# MikrofonZeWzmacniaczemSchematNowy2.net
KiCad netlist of a schematic drawn in EAGLE
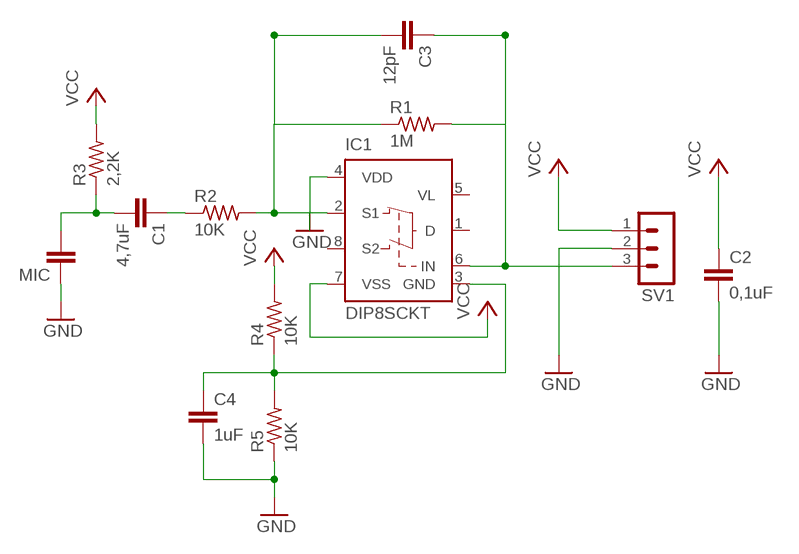
[diagram p0: schematic, sheet 1]

(export (version "E")
  (design (tool "Eeschema 10.0.6"))
  (components
    (comp (ref "C1")
      (value "4,7uF")
      (footprint "eagle-import:C0805")
      (libsource (lib "eagle-import") (part "C-EUC0805"))
    )
    (comp (ref "C2")
      (value "0,1uF")
      (footprint "eagle-import:C0805")
      (libsource (lib "eagle-import") (part "C-EUC0805"))
    )
    (comp (ref "C3")
      (value "12pF")
      (footprint "eagle-import:C0805")
      (libsource (lib "eagle-import") (part "C-EUC0805"))
    )
    (comp (ref "C4")
      (value "1uF")
      (footprint "eagle-import:C0805")
      (libsource (lib "eagle-import") (part "C-EUC0805"))
    )
    (comp (ref "IC1")
      (value "DIP8SCKT")
      (footprint "eagle-import:DIL08")
      (fields
        (field (name "MF") "ALTERA CORPORATION")
        (field (name "MPN") "ADG419BN")
        (field (name "MPN_1") "DIP8SOCKET")
      )
      (libsource (lib "eagle-import") (part "ADG419"))
    )
    (comp (ref "MIC")
      (value "C2.5/6")
      (footprint "eagle-import:C2.5-6")
      (libsource (lib "eagle-import") (part "C2.5/6"))
    )
    (comp (ref "R1")
      (value "1M")
      (footprint "eagle-import:R0805")
      (libsource (lib "eagle-import") (part "R-US_R0805"))
    )
    (comp (ref "R2")
      (value "10K")
      (footprint "eagle-import:R0805")
      (libsource (lib "eagle-import") (part "R-US_R0805"))
    )
    (comp (ref "R3")
      (value "2,2K")
      (footprint "eagle-import:R0805")
      (libsource (lib "eagle-import") (part "R-US_R0805"))
    )
    (comp (ref "R4")
      (value "10K")
      (footprint "eagle-import:R0805")
      (libsource (lib "eagle-import") (part "R-US_R0805"))
    )
    (comp (ref "R5")
      (value "10K")
      (footprint "eagle-import:R0805")
      (libsource (lib "eagle-import") (part "R-US_R0805"))
    )
    (comp (ref "SV1")
      (value "MA03-1")
      (footprint "eagle-import:MA03-1")
      (libsource (lib "eagle-import") (part "MA03-1"))
    )
  )
  (nets
    (net (code "1") (name "/VL") (class "Default")
      (node (ref "IC1") (pin "5") (pinfunction "VL_5") (pintype "power_in"))
    )
    (net (code "2") (name "GND") (class "Default")
      (node (ref "C2") (pin "2") (pinfunction "2_2") (pintype "passive"))
      (node (ref "C4") (pin "2") (pinfunction "2_2") (pintype "passive"))
      (node (ref "IC1") (pin "4") (pinfunction "VDD_4") (pintype "power_in"))
      (node (ref "MIC") (pin "1") (pinfunction "1_1") (pintype "passive"))
      (node (ref "R5") (pin "1") (pinfunction "1_1") (pintype "passive"))
      (node (ref "SV1") (pin "2") (pinfunction "2_2") (pintype "passive"))
    )
    (net (code "3") (name "Net-(C1-Pad1)") (class "Default")
      (node (ref "C1") (pin "1") (pinfunction "1_1") (pintype "passive"))
      (node (ref "R2") (pin "1") (pinfunction "1_1") (pintype "passive"))
    )
    (net (code "4") (name "Net-(C1-Pad2)") (class "Default")
      (node (ref "C1") (pin "2") (pinfunction "2_2") (pintype "passive"))
      (node (ref "MIC") (pin "2") (pinfunction "2_2") (pintype "passive"))
      (node (ref "R3") (pin "1") (pinfunction "1_1") (pintype "passive"))
    )
    (net (code "5") (name "Net-(IC1-GND)") (class "Default")
      (node (ref "C4") (pin "1") (pinfunction "1_1") (pintype "passive"))
      (node (ref "IC1") (pin "3") (pinfunction "GND_3") (pintype "power_in"))
      (node (ref "R4") (pin "1") (pinfunction "1_1") (pintype "passive"))
      (node (ref "R5") (pin "2") (pinfunction "2_2") (pintype "passive"))
    )
    (net (code "6") (name "Net-(IC1-IN)") (class "Default")
      (node (ref "C3") (pin "1") (pinfunction "1_1") (pintype "passive"))
      (node (ref "IC1") (pin "6") (pinfunction "IN_6") (pintype "input"))
      (node (ref "R1") (pin "2") (pinfunction "2_2") (pintype "passive"))
      (node (ref "SV1") (pin "3") (pinfunction "3_3") (pintype "passive"))
    )
    (net (code "7") (name "Net-(IC1-S1)") (class "Default")
      (node (ref "C3") (pin "2") (pinfunction "2_2") (pintype "passive"))
      (node (ref "IC1") (pin "2") (pinfunction "S1_2") (pintype "bidirectional"))
      (node (ref "R1") (pin "1") (pinfunction "1_1") (pintype "passive"))
      (node (ref "R2") (pin "2") (pinfunction "2_2") (pintype "passive"))
    )
    (net (code "8") (name "VCC") (class "Default")
      (node (ref "C2") (pin "1") (pinfunction "1_1") (pintype "passive"))
      (node (ref "IC1") (pin "7") (pinfunction "VSS_7") (pintype "power_in"))
      (node (ref "R3") (pin "2") (pinfunction "2_2") (pintype "passive"))
      (node (ref "R4") (pin "2") (pinfunction "2_2") (pintype "passive"))
      (node (ref "SV1") (pin "1") (pinfunction "1_1") (pintype "passive"))
    )
    (net (code "9") (name "unconnected-(IC1-D-Pad1)") (class "Default")
      (node (ref "IC1") (pin "1") (pinfunction "D_1") (pintype "bidirectional"))
    )
    (net (code "10") (name "unconnected-(IC1-S2-Pad8)") (class "Default")
      (node (ref "IC1") (pin "8") (pinfunction "S2_8") (pintype "bidirectional"))
    )
  )
)
